# PROC099B_Tempsensor.net
KiCad netlist of a schematic drawn in Altium Designer
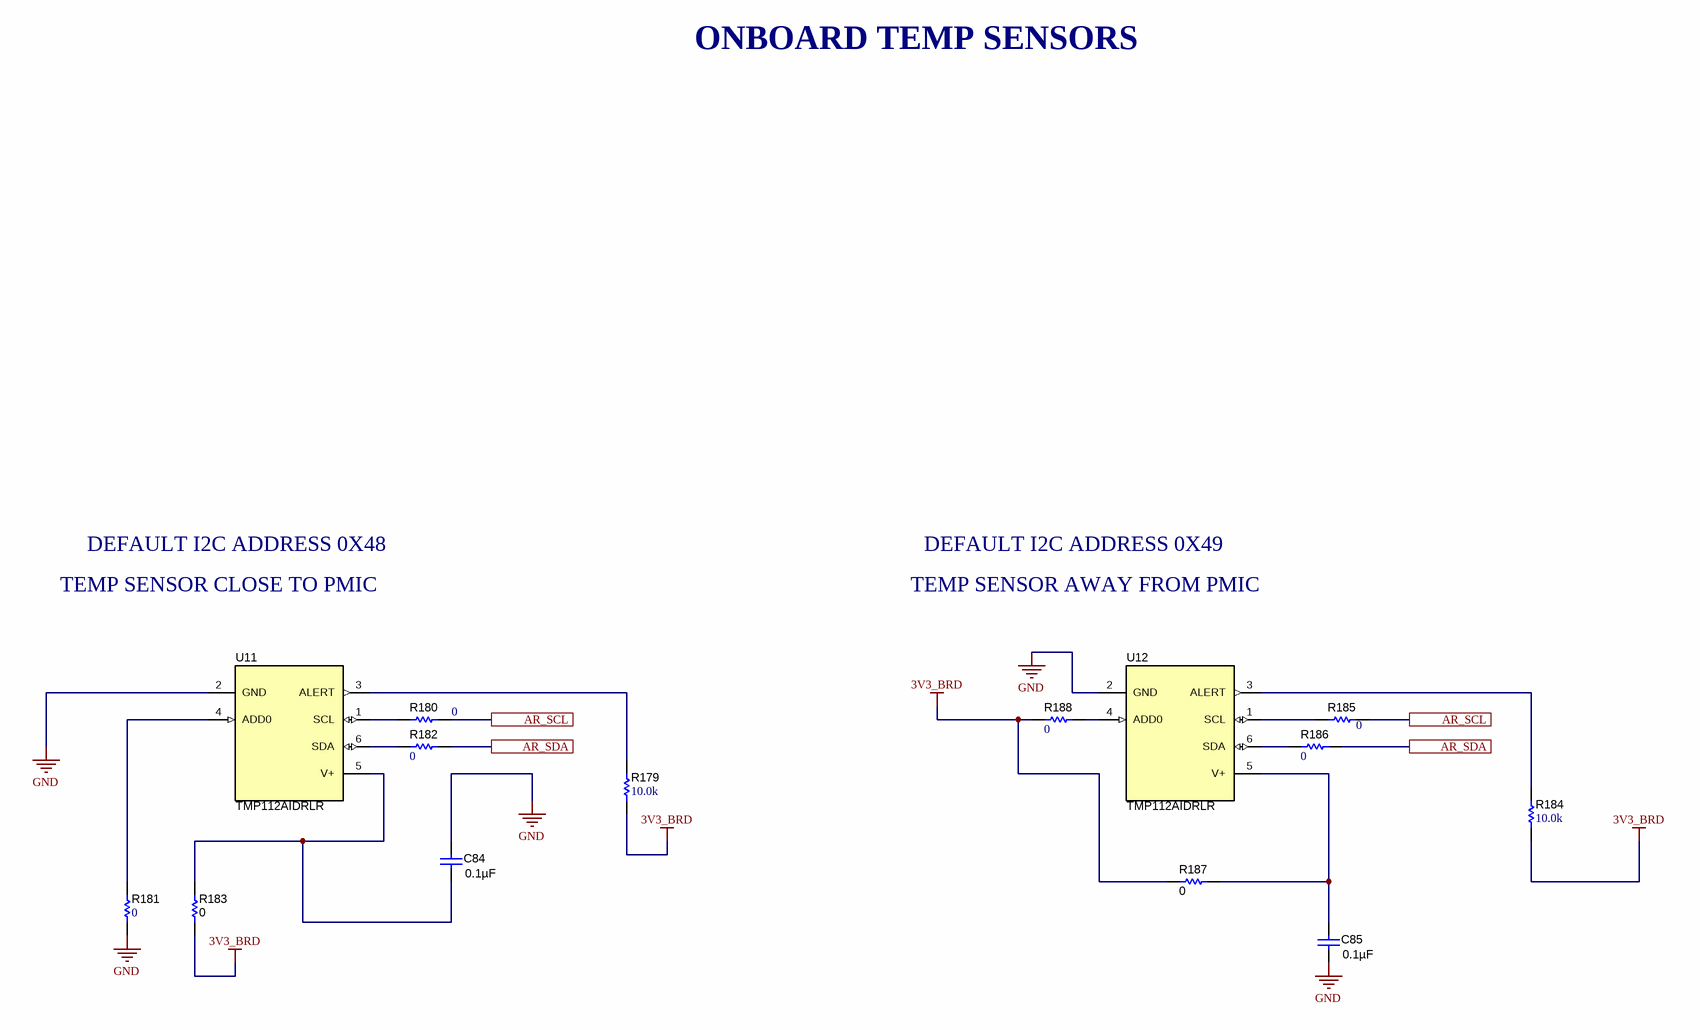
[diagram p0: PROC099B_Tempsensor.SchDoc]

(export (version "E")
  (design (tool "Eeschema 10.0.6"))
  (components
    (comp (ref "C84")
      (value "C0402C104K8RACTU")
      (footprint "0402L")
      (description "CAP, CERM, 0.1 µF, 10 V,+/- 10%, X7R, 0402")
      (fields (field (name "MANUFACTURER") "Kemet") (field (name "VALUEDISPLAYED") "0.1µF"))
      (libsource (lib "Altium Vault - TI") (part "Capacitor"))
    )
    (comp (ref "C85")
      (value "C0402C104K8RACTU")
      (footprint "0402L")
      (description "CAP, CERM, 0.1 µF, 10 V,+/- 10%, X7R, 0402")
      (fields (field (name "MANUFACTURER") "Kemet") (field (name "VALUEDISPLAYED") "0.1µF"))
      (libsource (lib "Altium Vault - TI") (part "Capacitor"))
    )
    (comp (ref "R179")
      (value "CRCW040210K0FKED")
      (footprint "0402L")
      (description "RES, 10.0 k, 1%, 0.063 W, AEC-Q200 Grade 0, 0402")
      (fields (field (name "MANUFACTURER") "Vishay-Dale") (field (name "VALUEDISPLAYED") "10.0k"))
      (libsource (lib "Altium Vault - TI") (part "Resistor"))
    )
    (comp (ref "R180")
      (value "CRCW02010000Z0ED")
      (footprint "0201_Silk")
      (description "RES, 0, 5%, 0.05 W, 0201")
      (fields (field (name "MANUFACTURER") "Vishay-Dale") (field (name "VALUEDISPLAYED") "0"))
      (libsource (lib "Altium Vault - TI") (part "Resistor"))
    )
    (comp (ref "R181")
      (value "CRCW02010000Z0ED")
      (footprint "0201_Silk")
      (description "RES, 0, 5%, 0.05 W, 0201")
      (fields (field (name "MANUFACTURER") "Vishay-Dale") (field (name "VALUEDISPLAYED") "0"))
      (libsource (lib "Altium Vault - TI") (part "Resistor"))
    )
    (comp (ref "R182")
      (value "CRCW02010000Z0ED")
      (footprint "0201_Silk")
      (description "RES, 0, 5%, 0.05 W, 0201")
      (fields (field (name "MANUFACTURER") "Vishay-Dale") (field (name "VALUEDISPLAYED") "0"))
      (libsource (lib "Altium Vault - TI") (part "Resistor"))
    )
    (comp (ref "R183")
      (value "ERJ-2GE0R00X")
      (footprint "0402L")
      (description "RES, 0, 5%, 0.063 W, 0402")
      (fields
        (field (name "MANUFACTURER") "Panasonic")
        (field (name "VALUEDISPLAYED") "0")
        (field (name "PUBLISHER") "Texas Instruments")
      )
      (libsource (lib "Altium Vault - TI") (part "Resistor"))
    )
    (comp (ref "R184")
      (value "CRCW040210K0FKED")
      (footprint "0402L")
      (description "RES, 10.0 k, 1%, 0.063 W, AEC-Q200 Grade 0, 0402")
      (fields (field (name "MANUFACTURER") "Vishay-Dale") (field (name "VALUEDISPLAYED") "10.0k"))
      (libsource (lib "Altium Vault - TI") (part "Resistor"))
    )
    (comp (ref "R185")
      (value "CRCW02010000Z0ED")
      (footprint "0201_Silk")
      (description "RES, 0, 5%, 0.05 W, 0201")
      (fields (field (name "MANUFACTURER") "Vishay-Dale") (field (name "VALUEDISPLAYED") "0"))
      (libsource (lib "Altium Vault - TI") (part "Resistor"))
    )
    (comp (ref "R186")
      (value "CRCW02010000Z0ED")
      (footprint "0201_Silk")
      (description "RES, 0, 5%, 0.05 W, 0201")
      (fields (field (name "MANUFACTURER") "Vishay-Dale") (field (name "VALUEDISPLAYED") "0"))
      (libsource (lib "Altium Vault - TI") (part "Resistor"))
    )
    (comp (ref "R187")
      (value "ERJ-2GE0R00X")
      (footprint "0402L")
      (description "RES, 0, 5%, 0.063 W, 0402")
      (fields
        (field (name "MANUFACTURER") "Panasonic")
        (field (name "VALUEDISPLAYED") "0")
        (field (name "PUBLISHER") "Texas Instruments")
      )
      (libsource (lib "Altium Vault - TI") (part "Resistor"))
    )
    (comp (ref "R188")
      (value "CRCW02010000Z0ED")
      (footprint "0201_Silk")
      (description "RES, 0, 5%, 0.05 W, 0201")
      (fields (field (name "MANUFACTURER") "Vishay-Dale") (field (name "VALUEDISPLAYED") "0"))
      (libsource (lib "Altium Vault - TI") (part "Resistor"))
    )
    (comp (ref "U11")
      (value "TMP112AIDRLR")
      (footprint "DRL0006A")
      (fields
        (field (name "ALTERNATE PARTNUMBER") "TMP112AIDRLT")
        (field (name "MANUFACTURER") "Texas Instruments")
        (field (name "PARTNUMBER") "TMP112AIDRLR")
        (field (name "PUBLISHER") "Texas Instruments")
      )
      (libsource (lib "Altium Vault - TI") (part "TMP112"))
    )
    (comp (ref "U12")
      (value "TMP112AIDRLR")
      (footprint "DRL0006A")
      (fields
        (field (name "ALTERNATE PARTNUMBER") "TMP112AIDRLT")
        (field (name "MANUFACTURER") "Texas Instruments")
        (field (name "PARTNUMBER") "TMP112AIDRLR")
        (field (name "PUBLISHER") "Texas Instruments")
      )
      (libsource (lib "Altium Vault - TI") (part "CMP-0067397-2"))
    )
  )
  (nets
    (net (code "1") (name "/AR_SCL") (class "Default")
      (node (ref "R180") (pin "1") (pinfunction "1_1") (pintype "passive"))
      (node (ref "R185") (pin "1") (pinfunction "1_1") (pintype "passive"))
    )
    (net (code "2") (name "/AR_SDA") (class "Default")
      (node (ref "R182") (pin "2") (pinfunction "2_2") (pintype "passive"))
      (node (ref "R186") (pin "2") (pinfunction "2_2") (pintype "passive"))
    )
    (net (code "3") (name "3V3_BRD") (class "Default")
      (node (ref "R179") (pin "2") (pinfunction "2_2") (pintype "passive"))
      (node (ref "R183") (pin "2") (pinfunction "2_2") (pintype "passive"))
      (node (ref "R184") (pin "2") (pinfunction "2_2") (pintype "passive"))
      (node (ref "R187") (pin "2") (pinfunction "2_2") (pintype "passive"))
      (node (ref "R188") (pin "1") (pinfunction "1_1") (pintype "passive"))
    )
    (net (code "4") (name "GND") (class "Default")
      (node (ref "C84") (pin "1") (pinfunction "1_1") (pintype "passive"))
      (node (ref "C85") (pin "2") (pinfunction "2_2") (pintype "passive"))
      (node (ref "R181") (pin "2") (pinfunction "2_2") (pintype "passive"))
      (node (ref "U11") (pin "2") (pinfunction "GND_2") (pintype "power_in"))
      (node (ref "U12") (pin "2") (pinfunction "GND_2") (pintype "power_in"))
    )
    (net (code "5") (name "Net-(U11-ADD0)") (class "Default")
      (node (ref "R181") (pin "1") (pinfunction "1_1") (pintype "passive"))
      (node (ref "U11") (pin "4") (pinfunction "ADD0_4") (pintype "input"))
    )
    (net (code "6") (name "Net-(U11-ALERT)") (class "Default")
      (node (ref "R179") (pin "1") (pinfunction "1_1") (pintype "passive"))
      (node (ref "U11") (pin "3") (pinfunction "ALERT_3") (pintype "output"))
    )
    (net (code "7") (name "Net-(U11-SCL)") (class "Default")
      (node (ref "R180") (pin "2") (pinfunction "2_2") (pintype "passive"))
      (node (ref "U11") (pin "1") (pinfunction "SCL_1") (pintype "bidirectional"))
    )
    (net (code "8") (name "Net-(U11-SDA)") (class "Default")
      (node (ref "R182") (pin "1") (pinfunction "1_1") (pintype "passive"))
      (node (ref "U11") (pin "6") (pinfunction "SDA_6") (pintype "bidirectional"))
    )
    (net (code "9") (name "Net-(U11-V+)") (class "Default")
      (node (ref "C84") (pin "2") (pinfunction "2_2") (pintype "passive"))
      (node (ref "R183") (pin "1") (pinfunction "1_1") (pintype "passive"))
      (node (ref "U11") (pin "5") (pinfunction "V+_5") (pintype "power_in"))
    )
    (net (code "10") (name "Net-(U12-ADD0)") (class "Default")
      (node (ref "R188") (pin "2") (pinfunction "2_2") (pintype "passive"))
      (node (ref "U12") (pin "4") (pinfunction "ADD0_4") (pintype "input"))
    )
    (net (code "11") (name "Net-(U12-ALERT)") (class "Default")
      (node (ref "R184") (pin "1") (pinfunction "1_1") (pintype "passive"))
      (node (ref "U12") (pin "3") (pinfunction "ALERT_3") (pintype "output"))
    )
    (net (code "12") (name "Net-(U12-SCL)") (class "Default")
      (node (ref "R185") (pin "2") (pinfunction "2_2") (pintype "passive"))
      (node (ref "U12") (pin "1") (pinfunction "SCL_1") (pintype "bidirectional"))
    )
    (net (code "13") (name "Net-(U12-SDA)") (class "Default")
      (node (ref "R186") (pin "1") (pinfunction "1_1") (pintype "passive"))
      (node (ref "U12") (pin "6") (pinfunction "SDA_6") (pintype "bidirectional"))
    )
    (net (code "14") (name "Net-(U12-V+)") (class "Default")
      (node (ref "C85") (pin "1") (pinfunction "1_1") (pintype "passive"))
      (node (ref "R187") (pin "1") (pinfunction "1_1") (pintype "passive"))
      (node (ref "U12") (pin "5") (pinfunction "V+_5") (pintype "power_in"))
    )
  )
)
